# ir2109.net
KiCad netlist of a schematic drawn in EAGLE
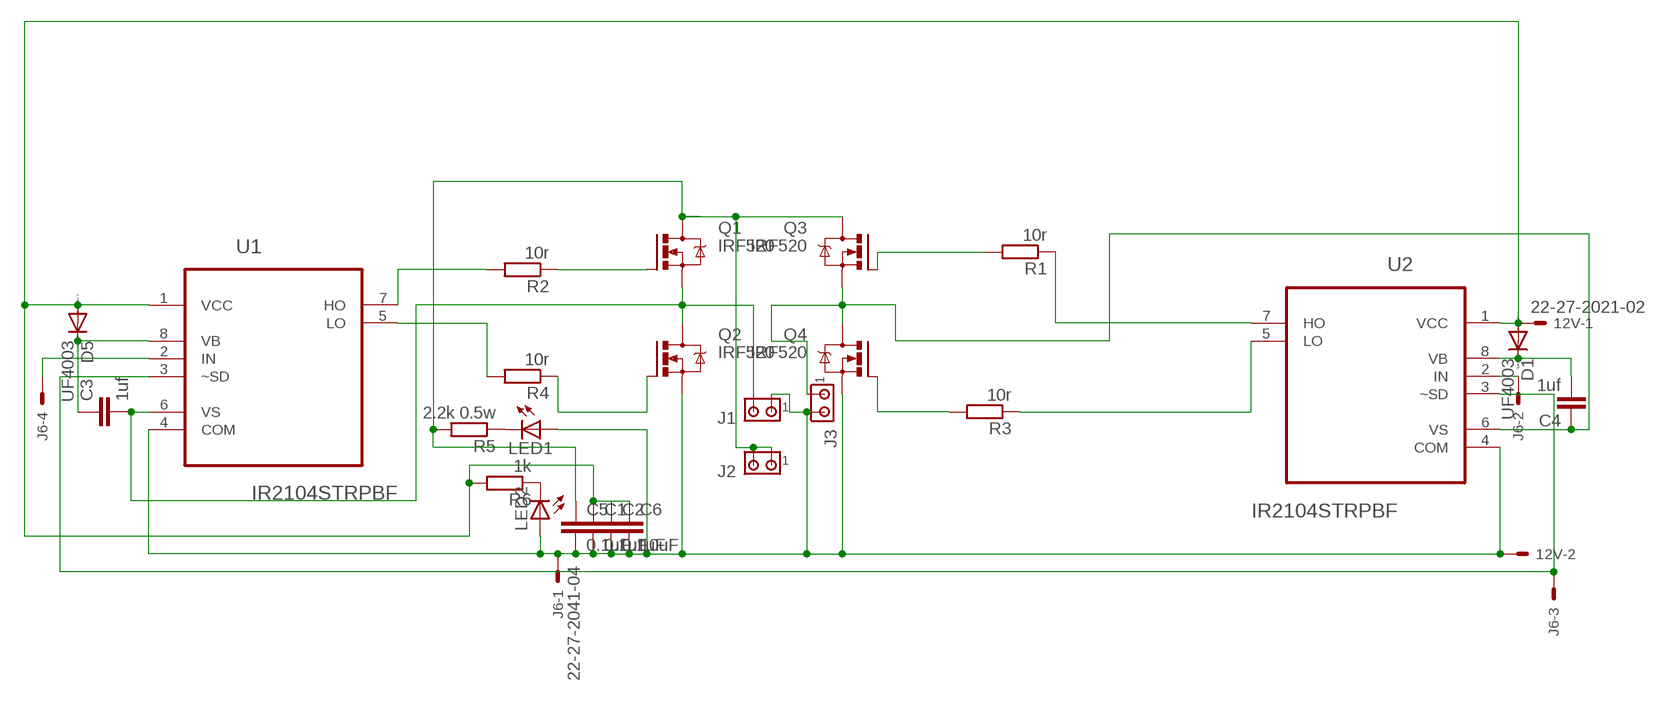
[diagram p0: schematic, sheet 1]

(export (version "E")
  (design (tool "Eeschema 10.0.6"))
  (components
    (comp (ref "12V")
      (value "22-27-2021-02")
      (footprint "eagle-import:6410-02")
      (libsource (lib "eagle-import") (part "22-?-0227-2021"))
    )
    (comp (ref "C1")
      (value "0.1uF")
      (footprint "eagle-import:C0805")
      (libsource (lib "eagle-import") (part "C-EUC0805"))
    )
    (comp (ref "C2")
      (value "0.1uF")
      (footprint "eagle-import:C0805")
      (libsource (lib "eagle-import") (part "C-EUC0805"))
    )
    (comp (ref "C3")
      (value "1uf")
      (footprint "eagle-import:C0805")
      (libsource (lib "eagle-import") (part "C-EUC0805"))
    )
    (comp (ref "C4")
      (value "1uf")
      (footprint "eagle-import:C0805")
      (libsource (lib "eagle-import") (part "C-EUC0805"))
    )
    (comp (ref "C5")
      (value "0.1uF")
      (footprint "eagle-import:C0805")
      (libsource (lib "eagle-import") (part "C-EUC0805"))
    )
    (comp (ref "C6")
      (value "10uF")
      (footprint "eagle-import:C5B7.2")
      (libsource (lib "eagle-import") (part "C5/7.2"))
    )
    (comp (ref "D1")
      (value "UF4003")
      (footprint "eagle-import:DO41-10")
      (libsource (lib "eagle-import") (part "UF4003"))
    )
    (comp (ref "D5")
      (value "UF4003")
      (footprint "eagle-import:DO41-10")
      (libsource (lib "eagle-import") (part "UF4003"))
    )
    (comp (ref "J1")
      (value "MTA02-156")
      (footprint "eagle-import:1X2MTA")
      (libsource (lib "eagle-import") (part "MTA02-156"))
    )
    (comp (ref "J2")
      (value "MTA02-156")
      (footprint "eagle-import:1X2MTA")
      (libsource (lib "eagle-import") (part "MTA02-156"))
    )
    (comp (ref "J3")
      (value "MTA02-156")
      (footprint "eagle-import:1X2MTA")
      (libsource (lib "eagle-import") (part "MTA02-156"))
    )
    (comp (ref "J6")
      (value "22-27-2041-04")
      (footprint "eagle-import:6410-04")
      (libsource (lib "eagle-import") (part "22-?-0427-2041"))
    )
    (comp (ref "LED1")
      (value "LEDCHIP-LED0603")
      (footprint "eagle-import:CHIP-LED0603")
      (libsource (lib "eagle-import") (part "LEDCHIP-LED0603"))
    )
    (comp (ref "LED2")
      (value "LEDCHIP-LED0603")
      (footprint "eagle-import:CHIP-LED0603")
      (libsource (lib "eagle-import") (part "LEDCHIP-LED0603"))
    )
    (comp (ref "Q1")
      (value "IRF520")
      (footprint "eagle-import:TO220BV")
      (libsource (lib "eagle-import") (part "IRF520"))
    )
    (comp (ref "Q2")
      (value "IRF520")
      (footprint "eagle-import:TO220BV")
      (libsource (lib "eagle-import") (part "IRF520"))
    )
    (comp (ref "Q3")
      (value "IRF520")
      (footprint "eagle-import:TO220BV")
      (libsource (lib "eagle-import") (part "IRF520"))
    )
    (comp (ref "Q4")
      (value "IRF520")
      (footprint "eagle-import:TO220BV")
      (libsource (lib "eagle-import") (part "IRF520"))
    )
    (comp (ref "R1")
      (value "10r")
      (footprint "eagle-import:R0805")
      (libsource (lib "eagle-import") (part "R-EU_R0805"))
    )
    (comp (ref "R2")
      (value "10r")
      (footprint "eagle-import:R0805")
      (libsource (lib "eagle-import") (part "R-EU_R0805"))
    )
    (comp (ref "R3")
      (value "10r")
      (footprint "eagle-import:R0805")
      (libsource (lib "eagle-import") (part "R-EU_R0805"))
    )
    (comp (ref "R4")
      (value "10r")
      (footprint "eagle-import:R0805")
      (libsource (lib "eagle-import") (part "R-EU_R0805"))
    )
    (comp (ref "R5")
      (value "2.2k 0.5w")
      (footprint "eagle-import:R1210")
      (libsource (lib "eagle-import") (part "R-EU_R1210"))
    )
    (comp (ref "R6")
      (value "1k")
      (footprint "eagle-import:R0805")
      (libsource (lib "eagle-import") (part "R-EU_R0805"))
    )
    (comp (ref "U1")
      (value "IR2104STRPBF")
      (footprint "eagle-import:SOIC127P600X175-8N")
      (libsource (lib "eagle-import") (part "IR2104STRPBF"))
    )
    (comp (ref "U2")
      (value "IR2104STRPBF")
      (footprint "eagle-import:SOIC127P600X175-8N")
      (libsource (lib "eagle-import") (part "IR2104STRPBF"))
    )
  )
  (nets
    (net (code "1") (name "Net-(12VA-S)") (class "Default")
      (node (ref "12V") (pin "1") (pinfunction "S_1") (pintype "passive"))
      (node (ref "C1") (pin "1") (pinfunction "1_1") (pintype "passive"))
      (node (ref "C2") (pin "1") (pinfunction "1_1") (pintype "passive"))
      (node (ref "C6") (pin "1") (pinfunction "1_1") (pintype "passive"))
      (node (ref "D1") (pin "A") (pinfunction "A_A") (pintype "passive"))
      (node (ref "D5") (pin "A") (pinfunction "A_A") (pintype "passive"))
      (node (ref "R6") (pin "2") (pinfunction "2_2") (pintype "passive"))
      (node (ref "U1") (pin "1") (pinfunction "VCC_1") (pintype "power_in"))
      (node (ref "U2") (pin "1") (pinfunction "VCC_1") (pintype "power_in"))
    )
    (net (code "2") (name "Net-(12VB-S)") (class "Default")
      (node (ref "12V") (pin "2") (pinfunction "S_2") (pintype "passive"))
      (node (ref "C1") (pin "2") (pinfunction "2_2") (pintype "passive"))
      (node (ref "C2") (pin "2") (pinfunction "2_2") (pintype "passive"))
      (node (ref "C5") (pin "2") (pinfunction "2_2") (pintype "passive"))
      (node (ref "C6") (pin "2") (pinfunction "2_2") (pintype "passive"))
      (node (ref "J1") (pin "1") (pinfunction "1_1") (pintype "passive"))
      (node (ref "J3") (pin "2") (pinfunction "2_2") (pintype "passive"))
      (node (ref "J6") (pin "1") (pinfunction "S_1") (pintype "passive"))
      (node (ref "LED1") (pin "A") (pinfunction "A_A") (pintype "passive"))
      (node (ref "LED2") (pin "A") (pinfunction "A_A") (pintype "passive"))
      (node (ref "Q2") (pin "S") (pinfunction "S_S") (pintype "passive"))
      (node (ref "Q4") (pin "S") (pinfunction "S_S") (pintype "passive"))
      (node (ref "U1") (pin "4") (pinfunction "COM_4") (pintype "passive"))
      (node (ref "U2") (pin "4") (pinfunction "COM_4") (pintype "passive"))
    )
    (net (code "3") (name "Net-(C5-Pad1)") (class "Default")
      (node (ref "C5") (pin "1") (pinfunction "1_1") (pintype "passive"))
      (node (ref "J2") (pin "1") (pinfunction "1_1") (pintype "passive"))
      (node (ref "J2") (pin "2") (pinfunction "2_2") (pintype "passive"))
      (node (ref "Q1") (pin "D") (pinfunction "D_D") (pintype "passive"))
      (node (ref "Q3") (pin "D") (pinfunction "D_D") (pintype "passive"))
      (node (ref "R5") (pin "2") (pinfunction "2_2") (pintype "passive"))
    )
    (net (code "4") (name "Net-(J6B-S)") (class "Default")
      (node (ref "J6") (pin "2") (pinfunction "S_2") (pintype "passive"))
      (node (ref "U2") (pin "2") (pinfunction "IN_2") (pintype "input"))
    )
    (net (code "5") (name "Net-(J6C-S)") (class "Default")
      (node (ref "J6") (pin "3") (pinfunction "S_3") (pintype "passive"))
      (node (ref "U1") (pin "3") (pinfunction "~{SD}_3") (pintype "input"))
      (node (ref "U2") (pin "3") (pinfunction "~{SD}_3") (pintype "input"))
    )
    (net (code "6") (name "Net-(J6D-S)") (class "Default")
      (node (ref "J6") (pin "4") (pinfunction "S_4") (pintype "passive"))
      (node (ref "U1") (pin "2") (pinfunction "IN_2") (pintype "input"))
    )
    (net (code "7") (name "Net-(LED1-PadC)") (class "Default")
      (node (ref "LED1") (pin "C") (pinfunction "C_C") (pintype "passive"))
      (node (ref "R5") (pin "1") (pinfunction "1_1") (pintype "passive"))
    )
    (net (code "8") (name "Net-(LED2-PadC)") (class "Default")
      (node (ref "LED2") (pin "C") (pinfunction "C_C") (pintype "passive"))
      (node (ref "R6") (pin "1") (pinfunction "1_1") (pintype "passive"))
    )
    (net (code "9") (name "Net-(Q1-PadG)") (class "Default")
      (node (ref "Q1") (pin "G") (pinfunction "G_G") (pintype "passive"))
      (node (ref "R2") (pin "1") (pinfunction "1_1") (pintype "passive"))
    )
    (net (code "10") (name "Net-(Q2-PadG)") (class "Default")
      (node (ref "Q2") (pin "G") (pinfunction "G_G") (pintype "passive"))
      (node (ref "R4") (pin "1") (pinfunction "1_1") (pintype "passive"))
    )
    (net (code "11") (name "Net-(Q3-PadG)") (class "Default")
      (node (ref "Q3") (pin "G") (pinfunction "G_G") (pintype "passive"))
      (node (ref "R1") (pin "2") (pinfunction "2_2") (pintype "passive"))
    )
    (net (code "12") (name "Net-(Q4-PadG)") (class "Default")
      (node (ref "Q4") (pin "G") (pinfunction "G_G") (pintype "passive"))
      (node (ref "R3") (pin "2") (pinfunction "2_2") (pintype "passive"))
    )
    (net (code "13") (name "Net-(U1-HO)") (class "Default")
      (node (ref "R2") (pin "2") (pinfunction "2_2") (pintype "passive"))
      (node (ref "U1") (pin "7") (pinfunction "HO_7") (pintype "output"))
    )
    (net (code "14") (name "Net-(U1-LO)") (class "Default")
      (node (ref "R4") (pin "2") (pinfunction "2_2") (pintype "passive"))
      (node (ref "U1") (pin "5") (pinfunction "LO_5") (pintype "output"))
    )
    (net (code "15") (name "Net-(U1-VB)") (class "Default")
      (node (ref "C3") (pin "1") (pinfunction "1_1") (pintype "passive"))
      (node (ref "D5") (pin "C") (pinfunction "C_C") (pintype "passive"))
      (node (ref "U1") (pin "8") (pinfunction "VB_8") (pintype "power_in"))
    )
    (net (code "16") (name "Net-(U1-VS)") (class "Default")
      (node (ref "C3") (pin "2") (pinfunction "2_2") (pintype "passive"))
      (node (ref "J1") (pin "2") (pinfunction "2_2") (pintype "passive"))
      (node (ref "Q1") (pin "S") (pinfunction "S_S") (pintype "passive"))
      (node (ref "Q2") (pin "D") (pinfunction "D_D") (pintype "passive"))
      (node (ref "U1") (pin "6") (pinfunction "VS_6") (pintype "power_in"))
    )
    (net (code "17") (name "Net-(U2-HO)") (class "Default")
      (node (ref "R1") (pin "1") (pinfunction "1_1") (pintype "passive"))
      (node (ref "U2") (pin "7") (pinfunction "HO_7") (pintype "output"))
    )
    (net (code "18") (name "Net-(U2-LO)") (class "Default")
      (node (ref "R3") (pin "1") (pinfunction "1_1") (pintype "passive"))
      (node (ref "U2") (pin "5") (pinfunction "LO_5") (pintype "output"))
    )
    (net (code "19") (name "Net-(U2-VB)") (class "Default")
      (node (ref "C4") (pin "2") (pinfunction "2_2") (pintype "passive"))
      (node (ref "D1") (pin "C") (pinfunction "C_C") (pintype "passive"))
      (node (ref "U2") (pin "8") (pinfunction "VB_8") (pintype "power_in"))
    )
    (net (code "20") (name "Net-(U2-VS)") (class "Default")
      (node (ref "C4") (pin "1") (pinfunction "1_1") (pintype "passive"))
      (node (ref "J3") (pin "1") (pinfunction "1_1") (pintype "passive"))
      (node (ref "Q3") (pin "S") (pinfunction "S_S") (pintype "passive"))
      (node (ref "Q4") (pin "D") (pinfunction "D_D") (pintype "passive"))
      (node (ref "U2") (pin "6") (pinfunction "VS_6") (pintype "power_in"))
    )
  )
)
